# LCL_sch.net
KiCad netlist of a schematic drawn in Altium Designer
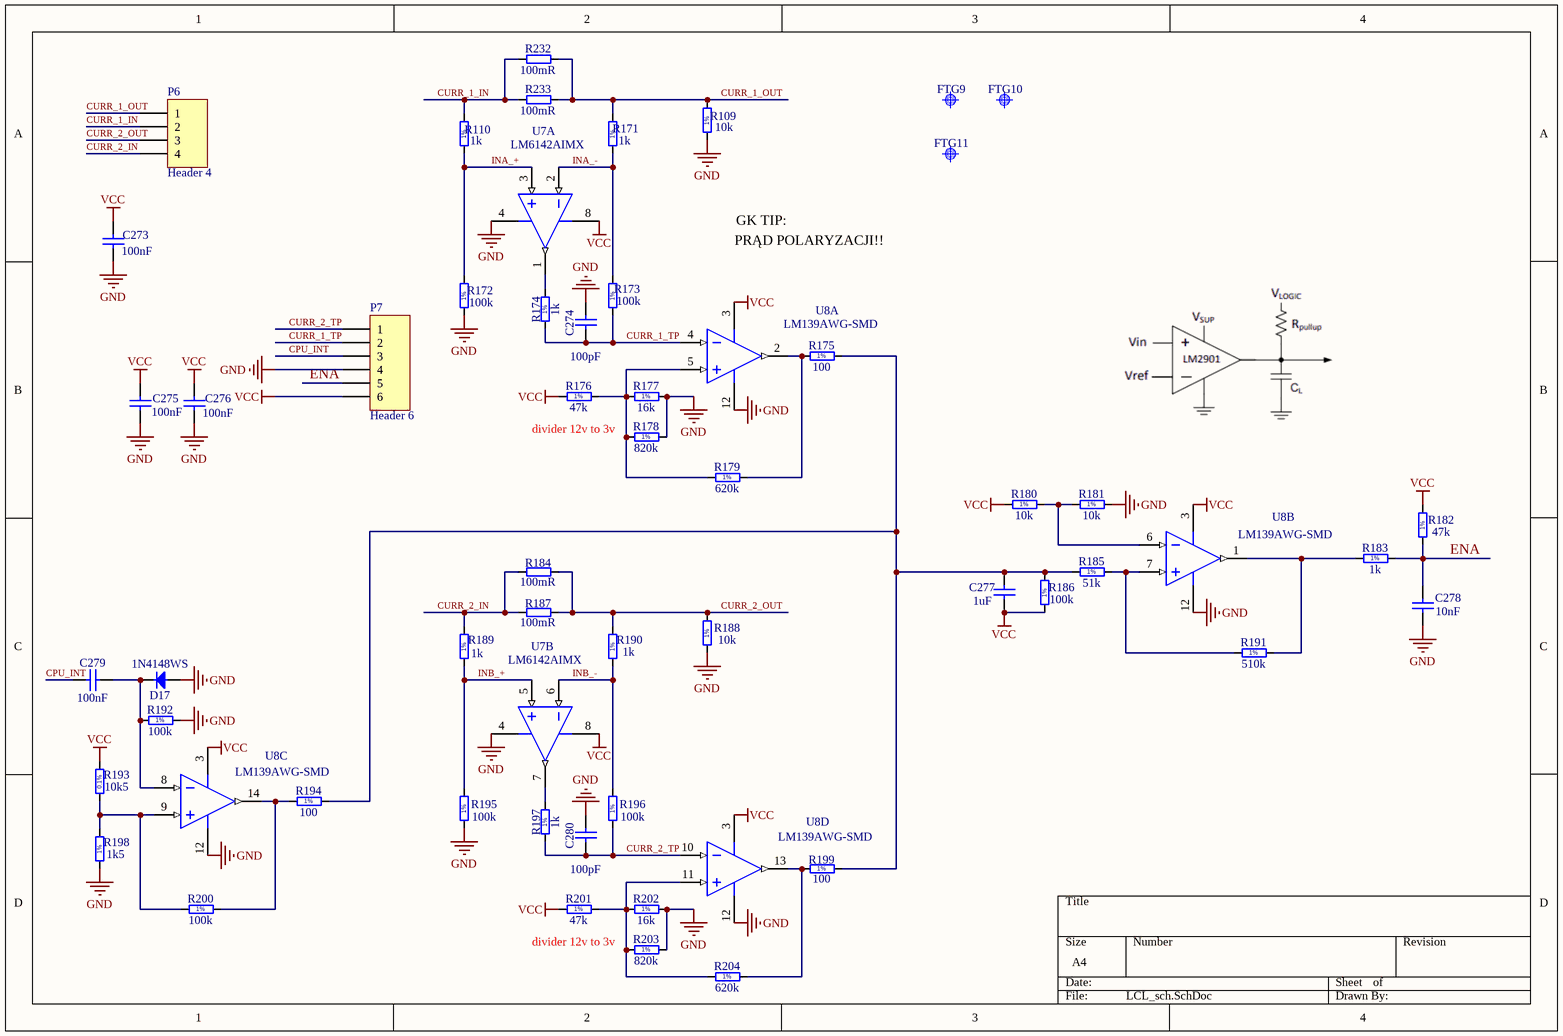
[diagram p0: LCL_sch.SchDoc]

(export (version "E")
  (design (tool "Eeschema 10.0.6"))
  (components
    (comp (ref "C273")
      (value "100nF")
      (footprint "CAPC1608X87N")
      (description "Non-polarised capacitor")
      (fields
        (field (name "PART NUMBER") "CC0603_100NF_50V_10%_X7R")
        (field (name "VOLTAGE") "50V")
        (field (name "AUTHOR") "CERN DEM JLC")
      )
      (libsource (lib "Capacitors") (part "Capacitor - non polarized"))
    )
    (comp (ref "C274")
      (value "100pF")
      (footprint "CAPC1608X87N")
      (description "Non-polarised capacitor")
      (fields
        (field (name "PART NUMBER") "CC0603_100PF_50V_10%_X7R")
        (field (name "VOLTAGE") "50V")
        (field (name "AUTHOR") "CERN DEM JLC")
      )
      (libsource (lib "Capacitors") (part "Capacitor - non polarized"))
    )
    (comp (ref "C275")
      (value "100nF")
      (footprint "CAPC1608X87N")
      (description "Non-polarised capacitor")
      (fields
        (field (name "PART NUMBER") "CC0603_100NF_50V_10%_X7R")
        (field (name "VOLTAGE") "50V")
        (field (name "AUTHOR") "CERN DEM JLC")
      )
      (libsource (lib "Capacitors") (part "Capacitor - non polarized"))
    )
    (comp (ref "C276")
      (value "100nF")
      (footprint "CAPC1608X87N")
      (description "Non-polarised capacitor")
      (fields
        (field (name "PART NUMBER") "CC0603_100NF_50V_10%_X7R")
        (field (name "VOLTAGE") "50V")
        (field (name "AUTHOR") "CERN DEM JLC")
      )
      (libsource (lib "Capacitors") (part "Capacitor - non polarized"))
    )
    (comp (ref "C277")
      (value "1uF")
      (footprint "CAPC1608X87N")
      (description "Non-polarised capacitor")
      (fields
        (field (name "PART NUMBER") "CC0603_1UF_25V_10%_X7R")
        (field (name "VOLTAGE") "25V")
        (field (name "AUTHOR") "CERN DEM JLC")
      )
      (libsource (lib "Capacitors") (part "Capacitor - non polarized"))
    )
    (comp (ref "C278")
      (value "10nF")
      (footprint "CAPC1608X87N")
      (description "Non-polarised capacitor")
      (fields
        (field (name "PART NUMBER") "CC0603_10NF_50V_10%_X7R")
        (field (name "VOLTAGE") "50V")
        (field (name "AUTHOR") "CERN DEM JLC")
      )
      (libsource (lib "Capacitors") (part "Capacitor - non polarized"))
    )
    (comp (ref "C279")
      (value "100nF")
      (footprint "CAPC1608X87N")
      (description "Non-polarised capacitor")
      (fields
        (field (name "PART NUMBER") "CC0603_100NF_50V_10%_X7R")
        (field (name "VOLTAGE") "50V")
        (field (name "AUTHOR") "CERN DEM JLC")
      )
      (libsource (lib "Capacitors") (part "Capacitor - non polarized"))
    )
    (comp (ref "C280")
      (value "100pF")
      (footprint "CAPC1608X87N")
      (description "Non-polarised capacitor")
      (fields
        (field (name "PART NUMBER") "CC0603_100PF_50V_10%_X7R")
        (field (name "VOLTAGE") "50V")
        (field (name "AUTHOR") "CERN DEM JLC")
      )
      (libsource (lib "Capacitors") (part "Capacitor - non polarized"))
    )
    (comp (ref "D17")
      (value "1N4148WS")
      (footprint "SODFL2512X100N")
      (description "Diode")
      (fields
        (field (name "VOLTAGE") "75V")
        (field (name "POWER") "150mA")
        (field (name "AUTHOR") "CERN DEM JLC")
      )
      (libsource (lib "ICs And Semiconductors") (part "Diode"))
    )
    (comp (ref "FTG9")
      (value "Use only in PCB")
      (footprint "FIDUCIAL_TOP_C100-200")
      (description "Fiducial Target")
      (fields (field (name "PART NUMBER") "FIDUCIAL_TARGET_C100-200") (field (name "AUTHOR") "CERN DEM JLC"))
      (libsource (lib "Eletro-mechanical") (part "Fiducial Target"))
    )
    (comp (ref "FTG10")
      (value "Use only in PCB")
      (footprint "FIDUCIAL_TOP_C100-200")
      (description "Fiducial Target")
      (fields (field (name "PART NUMBER") "FIDUCIAL_TARGET_C100-200") (field (name "AUTHOR") "CERN DEM JLC"))
      (libsource (lib "Eletro-mechanical") (part "Fiducial Target"))
    )
    (comp (ref "FTG11")
      (value "Use only in PCB")
      (footprint "FIDUCIAL_TOP_C100-200")
      (description "Fiducial Target")
      (fields (field (name "PART NUMBER") "FIDUCIAL_TARGET_C100-200") (field (name "AUTHOR") "CERN DEM JLC"))
      (libsource (lib "Eletro-mechanical") (part "Fiducial Target"))
    )
    (comp (ref "P6")
      (value "Header 4")
      (footprint "1x4 Header 2mm male")
      (description "Header, 4-Pin")
      (fields (field (name "PUBLISHER") "Altium Limited"))
      (libsource (lib "Connectors-headers") (part "Header 4"))
    )
    (comp (ref "P7")
      (value "Header 6")
      (footprint "2x3 Header 2mm male")
      (description "Header, 6-Pin")
      (fields (field (name "PUBLISHER") "Altium Limited"))
      (libsource (lib "Connectors-headers") (part "Header 6"))
    )
    (comp (ref "R109")
      (value "10k")
      (footprint "RESC1608X55N")
      (description "Resistor - 1%")
      (fields
        (field (name "PART NUMBER") "R0603_10K_1%_0.1W_100PPM")
        (field (name "POWER") "0.1W")
        (field (name "AUTHOR") "CERN DEM JLC")
      )
      (libsource (lib "Resistors") (part "Resistor - 1%"))
    )
    (comp (ref "R110")
      (value "1k")
      (footprint "RESC1608X55N")
      (description "Resistor - 1%")
      (fields
        (field (name "PART NUMBER") "R0603_1K_1%_0.1W_100PPM")
        (field (name "POWER") "0.1W")
        (field (name "AUTHOR") "CERN DEM JLC")
      )
      (libsource (lib "Resistors") (part "Resistor - 1%"))
    )
    (comp (ref "R171")
      (value "1k")
      (footprint "RESC1608X55N")
      (description "Resistor - 1%")
      (fields
        (field (name "PART NUMBER") "R0603_1K_1%_0.1W_100PPM")
        (field (name "POWER") "0.1W")
        (field (name "AUTHOR") "CERN DEM JLC")
      )
      (libsource (lib "Resistors") (part "Resistor - 1%"))
    )
    (comp (ref "R172")
      (value "100k")
      (footprint "RESC1608X55N")
      (description "Resistor - 1%")
      (fields
        (field (name "PART NUMBER") "R0603_100K_1%_0.1W_100PPM")
        (field (name "POWER") "0.1W")
        (field (name "AUTHOR") "CERN DEM JLC")
      )
      (libsource (lib "Resistors") (part "Resistor - 1%"))
    )
    (comp (ref "R173")
      (value "100k")
      (footprint "RESC1608X55N")
      (description "Resistor - 1%")
      (fields
        (field (name "PART NUMBER") "R0603_100K_1%_0.1W_100PPM")
        (field (name "POWER") "0.1W")
        (field (name "AUTHOR") "CERN DEM JLC")
      )
      (libsource (lib "Resistors") (part "Resistor - 1%"))
    )
    (comp (ref "R174")
      (value "1k")
      (footprint "RESC1608X55N")
      (description "Resistor - 1%")
      (fields
        (field (name "PART NUMBER") "R0603_1K_1%_0.1W_100PPM")
        (field (name "POWER") "0.1W")
        (field (name "AUTHOR") "CERN DEM JLC")
      )
      (libsource (lib "Resistors") (part "Resistor - 1%"))
    )
    (comp (ref "R175")
      (value "100")
      (footprint "RESC1608X55N")
      (description "Resistor - 1%")
      (fields
        (field (name "PART NUMBER") "R0603_100R_1%_0.1W_100PPM")
        (field (name "POWER") "0.1W")
        (field (name "AUTHOR") "CERN DEM JLC")
      )
      (libsource (lib "Resistors") (part "Resistor - 1%"))
    )
    (comp (ref "R176")
      (value "47k")
      (footprint "RESC1608X55N")
      (description "Resistor - 1%")
      (fields
        (field (name "PART NUMBER") "R0603_47K_1%_0.1W_100PPM")
        (field (name "POWER") "0.1W")
        (field (name "AUTHOR") "CERN DEM JLC")
      )
      (libsource (lib "Resistors") (part "Resistor - 1%"))
    )
    (comp (ref "R177")
      (value "16k")
      (footprint "RESC1608X55N")
      (description "Resistor - 1%")
      (fields
        (field (name "PART NUMBER") "R0603_16K_1%_0.1W_100PPM")
        (field (name "POWER") "0.1W")
        (field (name "AUTHOR") "CERN DEM JLC")
      )
      (libsource (lib "Resistors") (part "Resistor - 1%"))
    )
    (comp (ref "R178")
      (value "820k")
      (footprint "RESC1608X55N")
      (description "Resistor - 1%")
      (fields
        (field (name "PART NUMBER") "R0603_820K_1%_0.1W_100PPM")
        (field (name "POWER") "0.1W")
        (field (name "AUTHOR") "CERN DEM JLC")
      )
      (libsource (lib "Resistors") (part "Resistor - 1%"))
    )
    (comp (ref "R179")
      (value "620k")
      (footprint "RESC1608X55N")
      (description "Resistor - 1%")
      (fields
        (field (name "PART NUMBER") "R0603_620K_1%_0.1W_100PPM")
        (field (name "POWER") "0.1W")
        (field (name "AUTHOR") "CERN DEM JLC")
      )
      (libsource (lib "Resistors") (part "Resistor - 1%"))
    )
    (comp (ref "R180")
      (value "10k")
      (footprint "RESC1608X55N")
      (description "Resistor - 1%")
      (fields
        (field (name "PART NUMBER") "R0603_10K_1%_0.1W_100PPM")
        (field (name "POWER") "0.1W")
        (field (name "AUTHOR") "CERN DEM JLC")
      )
      (libsource (lib "Resistors") (part "Resistor - 1%"))
    )
    (comp (ref "R181")
      (value "10k")
      (footprint "RESC1608X55N")
      (description "Resistor - 1%")
      (fields
        (field (name "PART NUMBER") "R0603_10K_1%_0.1W_100PPM")
        (field (name "POWER") "0.1W")
        (field (name "AUTHOR") "CERN DEM JLC")
      )
      (libsource (lib "Resistors") (part "Resistor - 1%"))
    )
    (comp (ref "R182")
      (value "47k")
      (footprint "RESC1608X55N")
      (description "Resistor - 1%")
      (fields
        (field (name "PART NUMBER") "R0603_47K_1%_0.1W_100PPM")
        (field (name "POWER") "0.1W")
        (field (name "AUTHOR") "CERN DEM JLC")
      )
      (libsource (lib "Resistors") (part "Resistor - 1%"))
    )
    (comp (ref "R183")
      (value "1k")
      (footprint "RESC1608X55N")
      (description "Resistor - 1%")
      (fields
        (field (name "PART NUMBER") "R0603_1K_1%_0.1W_100PPM")
        (field (name "POWER") "0.1W")
        (field (name "AUTHOR") "CERN DEM JLC")
      )
      (libsource (lib "Resistors") (part "Resistor - 1%"))
    )
    (comp (ref "R184")
      (value "100mR")
      (footprint "RESC1608X55N")
      (description "Resistor")
      (fields
        (field (name "PART NUMBER") "100mR 0603")
        (field (name "MANUFACTURER") "GENERIC")
        (field (name "AUTHOR") "CERN DEM JLC")
      )
      (libsource (lib "Resistors") (part "Resistor"))
    )
    (comp (ref "R185")
      (value "51k")
      (footprint "RESC1608X55N")
      (description "Resistor - 1%")
      (fields
        (field (name "PART NUMBER") "R0603_51K_1%_0.1W_100PPM")
        (field (name "POWER") "0.1W")
        (field (name "AUTHOR") "CERN DEM JLC")
      )
      (libsource (lib "Resistors") (part "Resistor - 1%"))
    )
    (comp (ref "R186")
      (value "100k")
      (footprint "RESC1608X55N")
      (description "Resistor - 1%")
      (fields
        (field (name "PART NUMBER") "R0603_100K_1%_0.1W_100PPM")
        (field (name "POWER") "0.1W")
        (field (name "AUTHOR") "CERN DEM JLC")
      )
      (libsource (lib "Resistors") (part "Resistor - 1%"))
    )
    (comp (ref "R187")
      (value "100mR")
      (footprint "RESC1608X55N")
      (description "Resistor")
      (fields
        (field (name "PART NUMBER") "100mR 0603")
        (field (name "MANUFACTURER") "GENERIC")
        (field (name "AUTHOR") "CERN DEM JLC")
      )
      (libsource (lib "Resistors") (part "Resistor"))
    )
    (comp (ref "R188")
      (value "10k")
      (footprint "RESC1608X55N")
      (description "Resistor - 1%")
      (fields
        (field (name "PART NUMBER") "R0603_10K_1%_0.1W_100PPM")
        (field (name "POWER") "0.1W")
        (field (name "AUTHOR") "CERN DEM JLC")
      )
      (libsource (lib "Resistors") (part "Resistor - 1%"))
    )
    (comp (ref "R189")
      (value "1k")
      (footprint "RESC1608X55N")
      (description "Resistor - 1%")
      (fields
        (field (name "PART NUMBER") "R0603_1K_1%_0.1W_100PPM")
        (field (name "POWER") "0.1W")
        (field (name "AUTHOR") "CERN DEM JLC")
      )
      (libsource (lib "Resistors") (part "Resistor - 1%"))
    )
    (comp (ref "R190")
      (value "1k")
      (footprint "RESC1608X55N")
      (description "Resistor - 1%")
      (fields
        (field (name "PART NUMBER") "R0603_1K_1%_0.1W_100PPM")
        (field (name "POWER") "0.1W")
        (field (name "AUTHOR") "CERN DEM JLC")
      )
      (libsource (lib "Resistors") (part "Resistor - 1%"))
    )
    (comp (ref "R191")
      (value "510k")
      (footprint "RESC1608X55N")
      (description "Resistor - 1%")
      (fields
        (field (name "PART NUMBER") "R0603_510K_1%_0.1W_100PPM")
        (field (name "POWER") "0.1W")
        (field (name "AUTHOR") "CERN DEM JLC")
      )
      (libsource (lib "Resistors") (part "Resistor - 1%"))
    )
    (comp (ref "R192")
      (value "100k")
      (footprint "RESC1608X55N")
      (description "Resistor - 1%")
      (fields
        (field (name "PART NUMBER") "R0603_100K_1%_0.1W_100PPM")
        (field (name "POWER") "0.1W")
        (field (name "AUTHOR") "CERN DEM JLC")
      )
      (libsource (lib "Resistors") (part "Resistor - 1%"))
    )
    (comp (ref "R193")
      (value "10k5")
      (footprint "RESC1608X55N")
      (description "Resistor - 0.1%")
      (fields
        (field (name "PART NUMBER") "R0603_10K5_0.1%_0.063W_10PPM")
        (field (name "POWER") "0.063W")
        (field (name "AUTHOR") "CERN DEM JLC")
      )
      (libsource (lib "Resistors") (part "Resistor - 0.1%"))
    )
    (comp (ref "R194")
      (value "100")
      (footprint "RESC1608X55N")
      (description "Resistor - 1%")
      (fields
        (field (name "PART NUMBER") "R0603_100R_1%_0.1W_100PPM")
        (field (name "POWER") "0.1W")
        (field (name "AUTHOR") "CERN DEM JLC")
      )
      (libsource (lib "Resistors") (part "Resistor - 1%"))
    )
    (comp (ref "R195")
      (value "100k")
      (footprint "RESC1608X55N")
      (description "Resistor - 1%")
      (fields
        (field (name "PART NUMBER") "R0603_100K_1%_0.1W_100PPM")
        (field (name "POWER") "0.1W")
        (field (name "AUTHOR") "CERN DEM JLC")
      )
      (libsource (lib "Resistors") (part "Resistor - 1%"))
    )
    (comp (ref "R196")
      (value "100k")
      (footprint "RESC1608X55N")
      (description "Resistor - 1%")
      (fields
        (field (name "PART NUMBER") "R0603_100K_1%_0.1W_100PPM")
        (field (name "POWER") "0.1W")
        (field (name "AUTHOR") "CERN DEM JLC")
      )
      (libsource (lib "Resistors") (part "Resistor - 1%"))
    )
    (comp (ref "R197")
      (value "1k")
      (footprint "RESC1608X55N")
      (description "Resistor - 1%")
      (fields
        (field (name "PART NUMBER") "R0603_1K_1%_0.1W_100PPM")
        (field (name "POWER") "0.1W")
        (field (name "AUTHOR") "CERN DEM JLC")
      )
      (libsource (lib "Resistors") (part "Resistor - 1%"))
    )
    (comp (ref "R198")
      (value "1k5")
      (footprint "RESC1608X55N")
      (description "Resistor - 1%")
      (fields
        (field (name "PART NUMBER") "R0603_1K5_1%_0.1W_100PPM")
        (field (name "POWER") "0.1W")
        (field (name "AUTHOR") "CERN DEM JLC")
      )
      (libsource (lib "Resistors") (part "Resistor - 1%"))
    )
    (comp (ref "R199")
      (value "100")
      (footprint "RESC1608X55N")
      (description "Resistor - 1%")
      (fields
        (field (name "PART NUMBER") "R0603_100R_1%_0.1W_100PPM")
        (field (name "POWER") "0.1W")
        (field (name "AUTHOR") "CERN DEM JLC")
      )
      (libsource (lib "Resistors") (part "Resistor - 1%"))
    )
    (comp (ref "R200")
      (value "100k")
      (footprint "RESC1608X55N")
      (description "Resistor - 1%")
      (fields
        (field (name "PART NUMBER") "R0603_100K_1%_0.1W_100PPM")
        (field (name "POWER") "0.1W")
        (field (name "AUTHOR") "CERN DEM JLC")
      )
      (libsource (lib "Resistors") (part "Resistor - 1%"))
    )
    (comp (ref "R201")
      (value "47k")
      (footprint "RESC1608X55N")
      (description "Resistor - 1%")
      (fields
        (field (name "PART NUMBER") "R0603_47K_1%_0.1W_100PPM")
        (field (name "POWER") "0.1W")
        (field (name "AUTHOR") "CERN DEM JLC")
      )
      (libsource (lib "Resistors") (part "Resistor - 1%"))
    )
    (comp (ref "R202")
      (value "16k")
      (footprint "RESC1608X55N")
      (description "Resistor - 1%")
      (fields
        (field (name "PART NUMBER") "R0603_16K_1%_0.1W_100PPM")
        (field (name "POWER") "0.1W")
        (field (name "AUTHOR") "CERN DEM JLC")
      )
      (libsource (lib "Resistors") (part "Resistor - 1%"))
    )
    (comp (ref "R203")
      (value "820k")
      (footprint "RESC1608X55N")
      (description "Resistor - 1%")
      (fields
        (field (name "PART NUMBER") "R0603_820K_1%_0.1W_100PPM")
        (field (name "POWER") "0.1W")
        (field (name "AUTHOR") "CERN DEM JLC")
      )
      (libsource (lib "Resistors") (part "Resistor - 1%"))
    )
    (comp (ref "R204")
      (value "620k")
      (footprint "RESC1608X55N")
      (description "Resistor - 1%")
      (fields
        (field (name "PART NUMBER") "R0603_620K_1%_0.1W_100PPM")
        (field (name "POWER") "0.1W")
        (field (name "AUTHOR") "CERN DEM JLC")
      )
      (libsource (lib "Resistors") (part "Resistor - 1%"))
    )
    (comp (ref "R232")
      (value "100mR")
      (footprint "RESC1608X55N")
      (description "Resistor")
      (fields
        (field (name "PART NUMBER") "100mR 0603")
        (field (name "MANUFACTURER") "GENERIC")
        (field (name "AUTHOR") "CERN DEM JLC")
      )
      (libsource (lib "Resistors") (part "Resistor"))
    )
    (comp (ref "R233")
      (value "100mR")
      (footprint "RESC1608X55N")
      (description "Resistor")
      (fields
        (field (name "PART NUMBER") "100mR 0603")
        (field (name "MANUFACTURER") "GENERIC")
        (field (name "AUTHOR") "CERN DEM JLC")
      )
      (libsource (lib "Resistors") (part "Resistor"))
    )
    (comp (ref "U7")
      (value "LM6142AIMX")
      (footprint "M08A_N")
      (description "Dual High Speed/Low Power 17 MHz Rail-to-Rail I/O Operational Amplifier, 8-pin Narrow SOIC")
      (fields (field (name "MANUFACTURER") "National Semiconductor"))
      (libsource (lib "National Semiconductor Amplifier") (part "LM6142AIMX"))
    )
    (comp (ref "U8")
      (value "LM139AWG-SMD")
      (footprint "WG14A_N")
      (description "Low Power Low Offset Voltage Quad Comparator, 14-pin CerPACK")
      (fields (field (name "MANUFACTURER") "National Semiconductor"))
      (libsource (lib "National Semiconductor Amplifier") (part "LM139AWG-SMD"))
    )
  )
  (nets
    (net (code "1") (name "/CPU_INT") (class "Default")
      (node (ref "C279") (pin "1") (pinfunction "1_1") (pintype "passive"))
      (node (ref "P7") (pin "3") (pinfunction "3_3") (pintype "passive"))
    )
    (net (code "2") (name "/CURR_1_IN") (class "Default")
      (node (ref "P6") (pin "2") (pinfunction "2_2") (pintype "passive"))
      (node (ref "R110") (pin "2") (pinfunction "2_2") (pintype "passive"))
      (node (ref "R232") (pin "1") (pinfunction "1_1") (pintype "passive"))
      (node (ref "R233") (pin "1") (pinfunction "1_1") (pintype "passive"))
    )
    (net (code "3") (name "/CURR_1_OUT") (class "Default")
      (node (ref "P6") (pin "1") (pinfunction "1_1") (pintype "passive"))
      (node (ref "R109") (pin "2") (pinfunction "2_2") (pintype "passive"))
      (node (ref "R171") (pin "2") (pinfunction "2_2") (pintype "passive"))
      (node (ref "R232") (pin "2") (pinfunction "2_2") (pintype "passive"))
      (node (ref "R233") (pin "2") (pinfunction "2_2") (pintype "passive"))
    )
    (net (code "4") (name "/CURR_1_TP") (class "Default")
      (node (ref "C274") (pin "1") (pinfunction "1_1") (pintype "passive"))
      (node (ref "P7") (pin "2") (pinfunction "2_2") (pintype "passive"))
      (node (ref "R173") (pin "1") (pinfunction "1_1") (pintype "passive"))
      (node (ref "R174") (pin "1") (pinfunction "1_1") (pintype "passive"))
      (node (ref "U8") (pin "4") (pinfunction "IN1-_4") (pintype "input"))
    )
    (net (code "5") (name "/CURR_2_IN") (class "Default")
      (node (ref "P6") (pin "4") (pinfunction "4_4") (pintype "passive"))
      (node (ref "R184") (pin "1") (pinfunction "1_1") (pintype "passive"))
      (node (ref "R187") (pin "1") (pinfunction "1_1") (pintype "passive"))
      (node (ref "R189") (pin "2") (pinfunction "2_2") (pintype "passive"))
    )
    (net (code "6") (name "/CURR_2_OUT") (class "Default")
      (node (ref "P6") (pin "3") (pinfunction "3_3") (pintype "passive"))
      (node (ref "R184") (pin "2") (pinfunction "2_2") (pintype "passive"))
      (node (ref "R187") (pin "2") (pinfunction "2_2") (pintype "passive"))
      (node (ref "R188") (pin "2") (pinfunction "2_2") (pintype "passive"))
      (node (ref "R190") (pin "2") (pinfunction "2_2") (pintype "passive"))
    )
    (net (code "7") (name "/CURR_2_TP") (class "Default")
      (node (ref "C280") (pin "1") (pinfunction "1_1") (pintype "passive"))
      (node (ref "P7") (pin "1") (pinfunction "1_1") (pintype "passive"))
      (node (ref "R196") (pin "1") (pinfunction "1_1") (pintype "passive"))
      (node (ref "R197") (pin "1") (pinfunction "1_1") (pintype "passive"))
      (node (ref "U8") (pin "10") (pinfunction "IN4-_10") (pintype "input"))
    )
    (net (code "8") (name "/ENA") (class "Default")
      (node (ref "C278") (pin "2") (pinfunction "2_2") (pintype "passive"))
      (node (ref "P7") (pin "5") (pinfunction "5_5") (pintype "passive"))
      (node (ref "R182") (pin "1") (pinfunction "1_1") (pintype "passive"))
      (node (ref "R183") (pin "2") (pinfunction "2_2") (pintype "passive"))
    )
    (net (code "9") (name "/INA_+") (class "Default")
      (node (ref "R110") (pin "1") (pinfunction "1_1") (pintype "passive"))
      (node (ref "R172") (pin "2") (pinfunction "2_2") (pintype "passive"))
      (node (ref "U7") (pin "3") (pinfunction "INA+_3") (pintype "input"))
    )
    (net (code "10") (name "/INA_-") (class "Default")
      (node (ref "R171") (pin "1") (pinfunction "1_1") (pintype "passive"))
      (node (ref "R173") (pin "2") (pinfunction "2_2") (pintype "passive"))
      (node (ref "U7") (pin "2") (pinfunction "INA-_2") (pintype "input"))
    )
    (net (code "11") (name "/INB_+") (class "Default")
      (node (ref "R189") (pin "1") (pinfunction "1_1") (pintype "passive"))
      (node (ref "R195") (pin "2") (pinfunction "2_2") (pintype "passive"))
      (node (ref "U7") (pin "5") (pinfunction "INB+_5") (pintype "input"))
    )
    (net (code "12") (name "/INB_-") (class "Default")
      (node (ref "R190") (pin "1") (pinfunction "1_1") (pintype "passive"))
      (node (ref "R196") (pin "2") (pinfunction "2_2") (pintype "passive"))
      (node (ref "U7") (pin "6") (pinfunction "INB-_6") (pintype "input"))
    )
    (net (code "13") (name "GND") (class "Default")
      (node (ref "C273") (pin "1") (pinfunction "1_1") (pintype "passive"))
      (node (ref "C274") (pin "2") (pinfunction "2_2") (pintype "passive"))
      (node (ref "C275") (pin "1") (pinfunction "1_1") (pintype "passive"))
      (node (ref "C276") (pin "1") (pinfunction "1_1") (pintype "passive"))
      (node (ref "C278") (pin "1") (pinfunction "1_1") (pintype "passive"))
      (node (ref "C280") (pin "2") (pinfunction "2_2") (pintype "passive"))
      (node (ref "D17") (pin "2") (pinfunction "A_2") (pintype "passive"))
      (node (ref "P7") (pin "4") (pinfunction "4_4") (pintype "passive"))
      (node (ref "R109") (pin "1") (pinfunction "1_1") (pintype "passive"))
      (node (ref "R172") (pin "1") (pinfunction "1_1") (pintype "passive"))
      (node (ref "R177") (pin "2") (pinfunction "2_2") (pintype "passive"))
      (node (ref "R178") (pin "2") (pinfunction "2_2") (pintype "passive"))
      (node (ref "R181") (pin "2") (pinfunction "2_2") (pintype "passive"))
      (node (ref "R188") (pin "1") (pinfunction "1_1") (pintype "passive"))
      (node (ref "R192") (pin "2") (pinfunction "2_2") (pintype "passive"))
      (node (ref "R195") (pin "1") (pinfunction "1_1") (pintype "passive"))
      (node (ref "R198") (pin "1") (pinfunction "1_1") (pintype "passive"))
      (node (ref "R202") (pin "2") (pinfunction "2_2") (pintype "passive"))
      (node (ref "R203") (pin "2") (pinfunction "2_2") (pintype "passive"))
      (node (ref "U7") (pin "4") (pinfunction "V-_4") (pintype "power_in"))
      (node (ref "U8") (pin "12") (pinfunction "GND_12") (pintype "power_in"))
    )
    (net (code "14") (name "Net-(C277-Pad2)") (class "Default")
      (node (ref "C277") (pin "2") (pinfunction "2_2") (pintype "passive"))
      (node (ref "R175") (pin "2") (pinfunction "2_2") (pintype "passive"))
      (node (ref "R185") (pin "1") (pinfunction "1_1") (pintype "passive"))
      (node (ref "R186") (pin "2") (pinfunction "2_2") (pintype "passive"))
      (node (ref "R194") (pin "2") (pinfunction "2_2") (pintype "passive"))
      (node (ref "R199") (pin "2") (pinfunction "2_2") (pintype "passive"))
    )
    (net (code "15") (name "Net-(D17-C)") (class "Default")
      (node (ref "C279") (pin "2") (pinfunction "2_2") (pintype "passive"))
      (node (ref "D17") (pin "1") (pinfunction "C_1") (pintype "passive"))
      (node (ref "R192") (pin "1") (pinfunction "1_1") (pintype "passive"))
      (node (ref "U8") (pin "8") (pinfunction "IN3-_8") (pintype "input"))
    )
    (net (code "16") (name "Net-(U7A-OUTA)") (class "Default")
      (node (ref "R174") (pin "2") (pinfunction "2_2") (pintype "passive"))
      (node (ref "U7") (pin "1") (pinfunction "OUTA_1") (pintype "output"))
    )
    (net (code "17") (name "Net-(U7B-OUTB)") (class "Default")
      (node (ref "R197") (pin "2") (pinfunction "2_2") (pintype "passive"))
      (node (ref "U7") (pin "7") (pinfunction "OUTB_7") (pintype "output"))
    )
    (net (code "18") (name "Net-(U8A-IN1+)") (class "Default")
      (node (ref "R176") (pin "2") (pinfunction "2_2") (pintype "passive"))
      (node (ref "R177") (pin "1") (pinfunction "1_1") (pintype "passive"))
      (node (ref "R178") (pin "1") (pinfunction "1_1") (pintype "passive"))
      (node (ref "R179") (pin "1") (pinfunction "1_1") (pintype "passive"))
      (node (ref "U8") (pin "5") (pinfunction "IN1+_5") (pintype "input"))
    )
    (net (code "19") (name "Net-(U8A-OUT1)") (class "Default")
      (node (ref "R175") (pin "1") (pinfunction "1_1") (pintype "passive"))
      (node (ref "R179") (pin "2") (pinfunction "2_2") (pintype "passive"))
      (node (ref "U8") (pin "2") (pinfunction "OUT1_2") (pintype "output"))
    )
    (net (code "20") (name "Net-(U8B-IN2+)") (class "Default")
      (node (ref "R185") (pin "2") (pinfunction "2_2") (pintype "passive"))
      (node (ref "R191") (pin "1") (pinfunction "1_1") (pintype "passive"))
      (node (ref "U8") (pin "7") (pinfunction "IN2+_7") (pintype "input"))
    )
    (net (code "21") (name "Net-(U8B-IN2-)") (class "Default")
      (node (ref "R180") (pin "2") (pinfunction "2_2") (pintype "passive"))
      (node (ref "R181") (pin "1") (pinfunction "1_1") (pintype "passive"))
      (node (ref "U8") (pin "6") (pinfunction "IN2-_6") (pintype "input"))
    )
    (net (code "22") (name "Net-(U8B-OUT2)") (class "Default")
      (node (ref "R183") (pin "1") (pinfunction "1_1") (pintype "passive"))
      (node (ref "R191") (pin "2") (pinfunction "2_2") (pintype "passive"))
      (node (ref "U8") (pin "1") (pinfunction "OUT2_1") (pintype "output"))
    )
    (net (code "23") (name "Net-(U8C-IN3+)") (class "Default")
      (node (ref "R193") (pin "1") (pinfunction "1_1") (pintype "passive"))
      (node (ref "R198") (pin "2") (pinfunction "2_2") (pintype "passive"))
      (node (ref "R200") (pin "1") (pinfunction "1_1") (pintype "passive"))
      (node (ref "U8") (pin "9") (pinfunction "IN3+_9") (pintype "input"))
    )
    (net (code "24") (name "Net-(U8C-OUT3)") (class "Default")
      (node (ref "R194") (pin "1") (pinfunction "1_1") (pintype "passive"))
      (node (ref "R200") (pin "2") (pinfunction "2_2") (pintype "passive"))
      (node (ref "U8") (pin "14") (pinfunction "OUT3_14") (pintype "output"))
    )
    (net (code "25") (name "Net-(U8D-IN4+)") (class "Default")
      (node (ref "R201") (pin "2") (pinfunction "2_2") (pintype "passive"))
      (node (ref "R202") (pin "1") (pinfunction "1_1") (pintype "passive"))
      (node (ref "R203") (pin "1") (pinfunction "1_1") (pintype "passive"))
      (node (ref "R204") (pin "1") (pinfunction "1_1") (pintype "passive"))
      (node (ref "U8") (pin "11") (pinfunction "IN4+_11") (pintype "input"))
    )
    (net (code "26") (name "Net-(U8D-OUT4)") (class "Default")
      (node (ref "R199") (pin "1") (pinfunction "1_1") (pintype "passive"))
      (node (ref "R204") (pin "2") (pinfunction "2_2") (pintype "passive"))
      (node (ref "U8") (pin "13") (pinfunction "OUT4_13") (pintype "output"))
    )
    (net (code "27") (name "VCC") (class "Default")
      (node (ref "C273") (pin "2") (pinfunction "2_2") (pintype "passive"))
      (node (ref "C275") (pin "2") (pinfunction "2_2") (pintype "passive"))
      (node (ref "C276") (pin "2") (pinfunction "2_2") (pintype "passive"))
      (node (ref "C277") (pin "1") (pinfunction "1_1") (pintype "passive"))
      (node (ref "P7") (pin "6") (pinfunction "6_6") (pintype "passive"))
      (node (ref "R176") (pin "1") (pinfunction "1_1") (pintype "passive"))
      (node (ref "R180") (pin "1") (pinfunction "1_1") (pintype "passive"))
      (node (ref "R182") (pin "2") (pinfunction "2_2") (pintype "passive"))
      (node (ref "R186") (pin "1") (pinfunction "1_1") (pintype "passive"))
      (node (ref "R193") (pin "2") (pinfunction "2_2") (pintype "passive"))
      (node (ref "R201") (pin "1") (pinfunction "1_1") (pintype "passive"))
      (node (ref "U7") (pin "8") (pinfunction "V+_8") (pintype "power_in"))
      (node (ref "U8") (pin "3") (pinfunction "V+_3") (pintype "power_in"))
    )
  )
)
